# FMC_Connector.net
KiCad netlist of a schematic drawn in Altium Designer
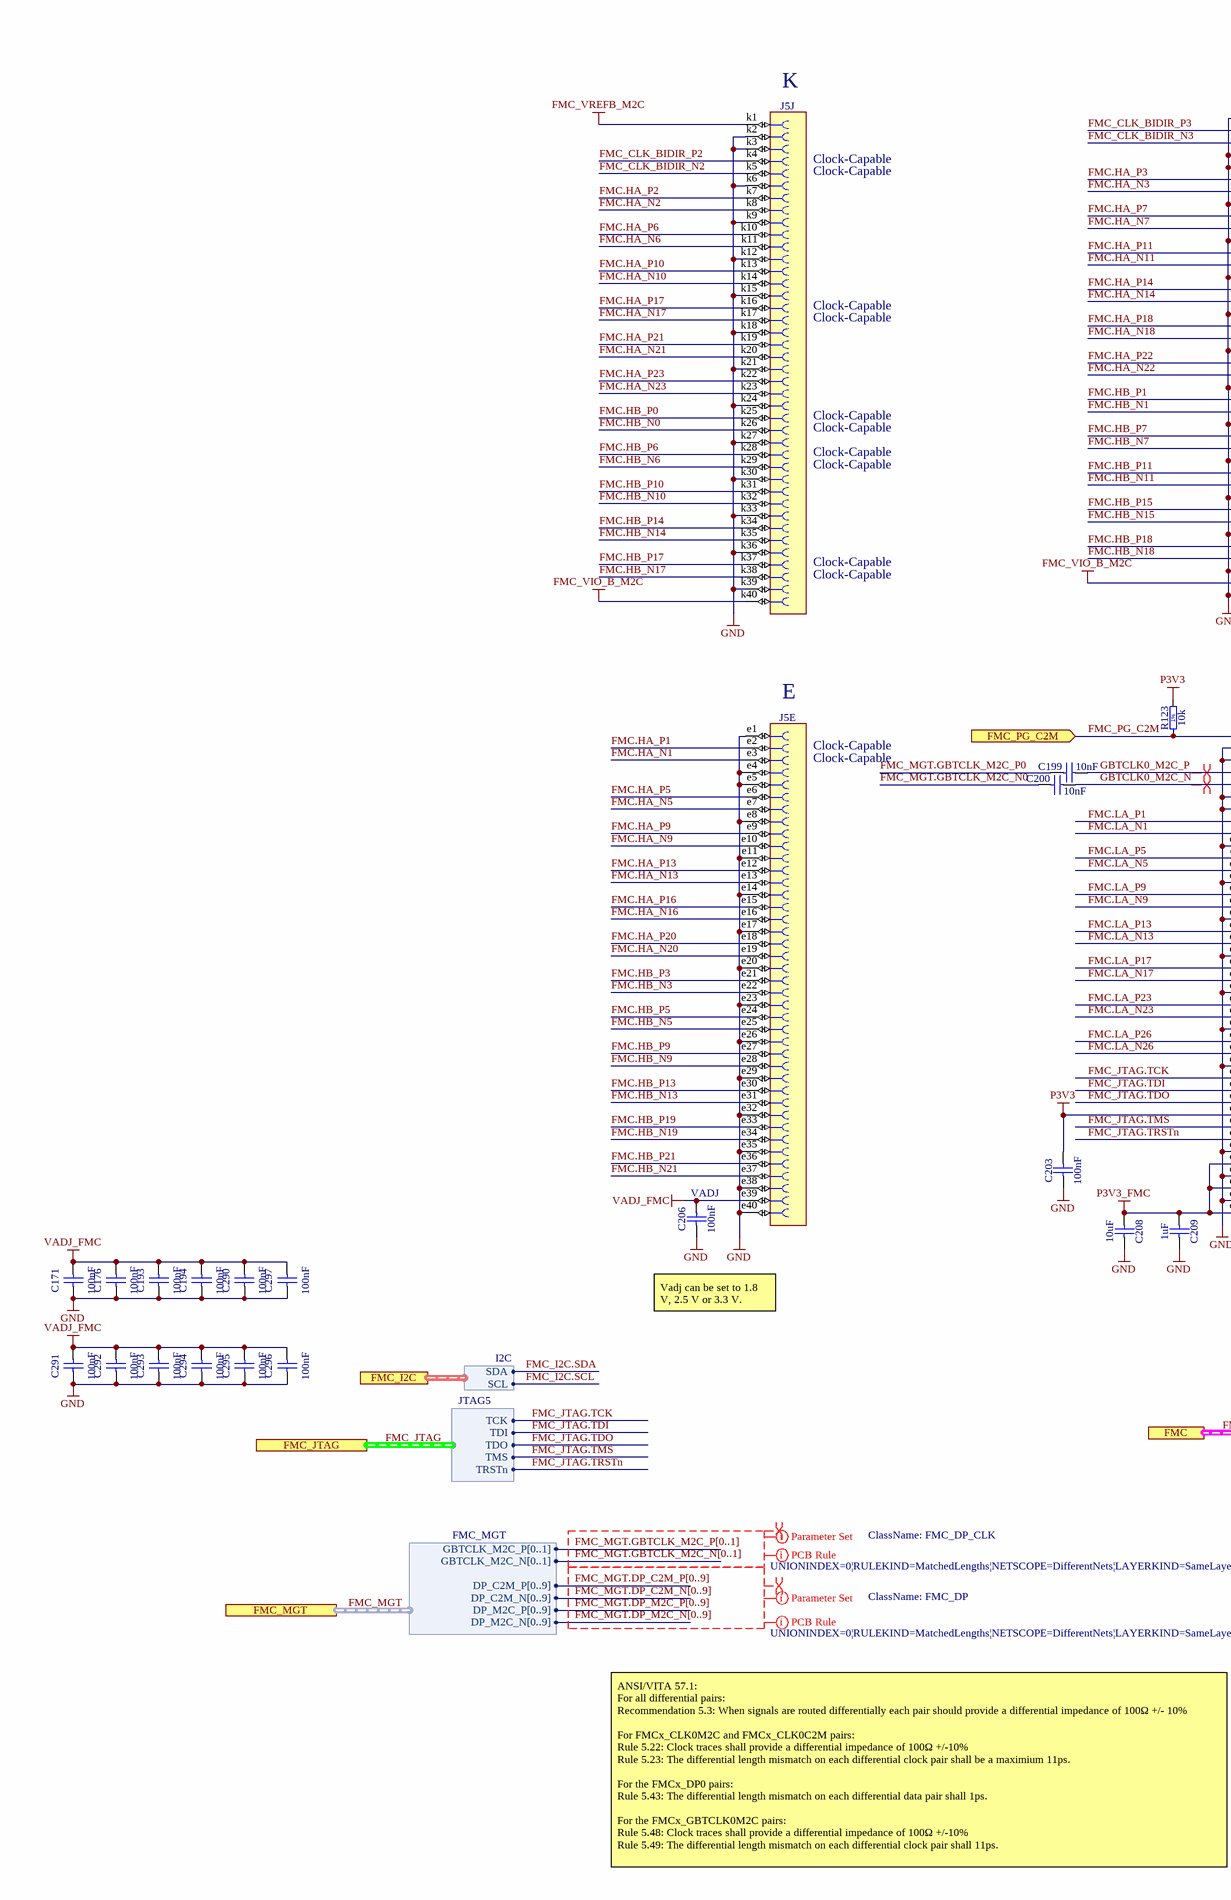
[diagram p0: FMC_Connector.SchDoc, left]
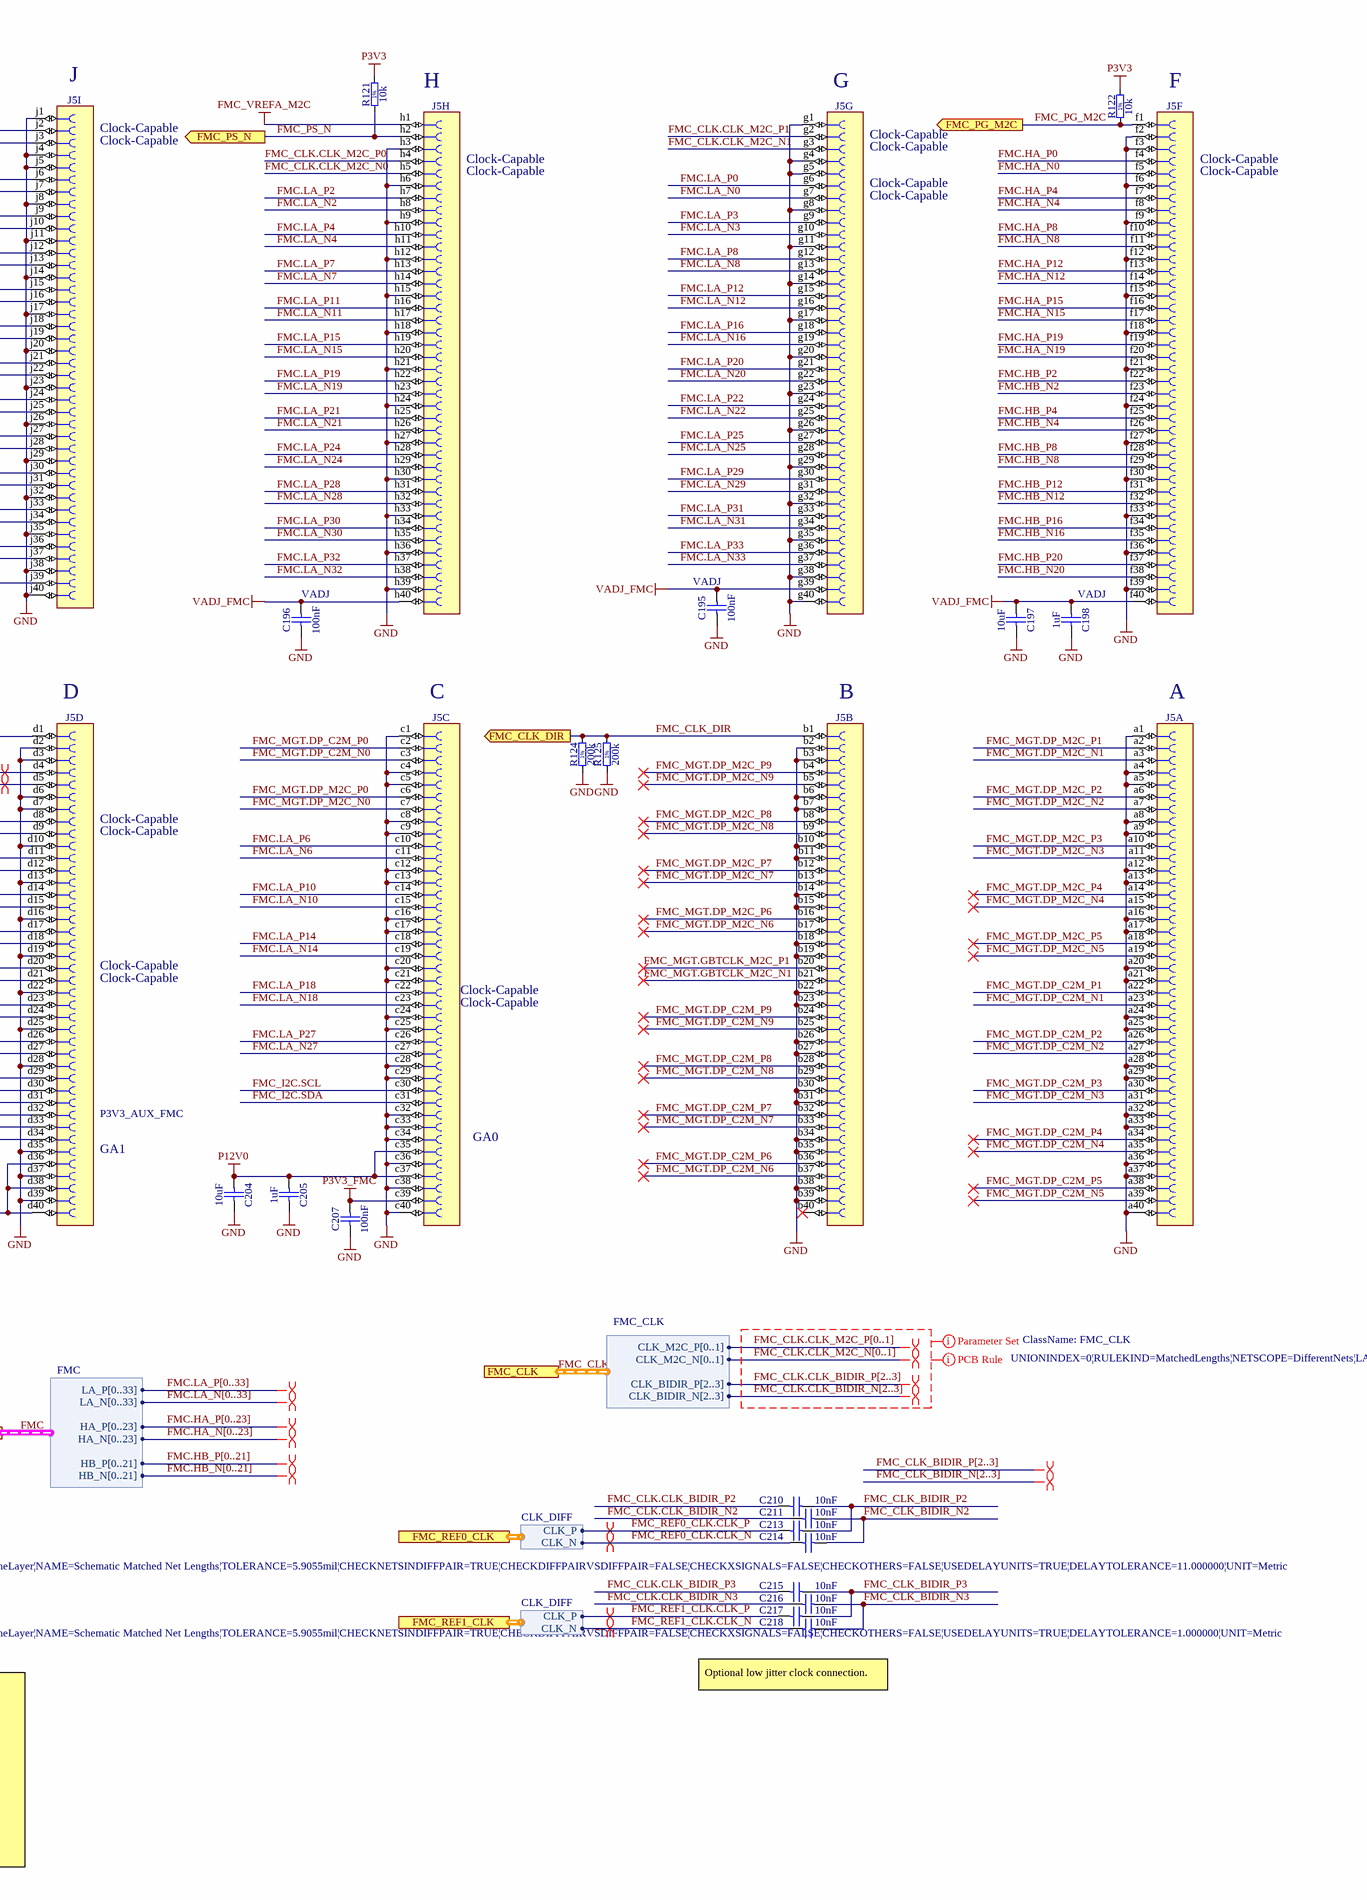
[diagram p1: FMC_Connector.SchDoc, right]

(export (version "E")
  (design (tool "Eeschema 10.0.6"))
  (components
    (comp (ref "C171")
      (value "100nF")
      (footprint "CAPC0603X33N")
      (description "Non-polarised capacitor")
      (fields
        (field (name "PART NUMBER") "CC0201_100NF_6.3V_10%_X5R")
        (field (name "VOLTAGE") "6.3V")
        (field (name "AUTHOR") "CERN DEM JLC")
      )
      (libsource (lib "Capacitors") (part "Capacitor - non polarized"))
    )
    (comp (ref "C176")
      (value "100nF")
      (footprint "CAPC0603X33N")
      (description "Non-polarised capacitor")
      (fields
        (field (name "PART NUMBER") "CC0201_100NF_6.3V_10%_X5R")
        (field (name "VOLTAGE") "6.3V")
        (field (name "AUTHOR") "CERN DEM JLC")
      )
      (libsource (lib "Capacitors") (part "Capacitor - non polarized"))
    )
    (comp (ref "C193")
      (value "100nF")
      (footprint "CAPC0603X33N")
      (description "Non-polarised capacitor")
      (fields
        (field (name "PART NUMBER") "CC0201_100NF_6.3V_10%_X5R")
        (field (name "VOLTAGE") "6.3V")
        (field (name "AUTHOR") "CERN DEM JLC")
      )
      (libsource (lib "Capacitors") (part "Capacitor - non polarized"))
    )
    (comp (ref "C194")
      (value "100nF")
      (footprint "CAPC0603X33N")
      (description "Non-polarised capacitor")
      (fields
        (field (name "PART NUMBER") "CC0201_100NF_6.3V_10%_X5R")
        (field (name "VOLTAGE") "6.3V")
        (field (name "AUTHOR") "CERN DEM JLC")
      )
      (libsource (lib "Capacitors") (part "Capacitor - non polarized"))
    )
    (comp (ref "C195")
      (value "100nF")
      (footprint "CAPC1005X55N")
      (description "Non-polarised capacitor")
      (fields
        (field (name "PART NUMBER") "CC0402_100NF_25V_10%_X7R_YUDEN_TMK105B7104KVHF")
        (field (name "VOLTAGE") "25V")
        (field (name "AUTHOR") "CERN DEM JLC")
      )
      (libsource (lib "Capacitors") (part "Capacitor - non polarized"))
    )
    (comp (ref "C196")
      (value "100nF")
      (footprint "CAPC1005X55N")
      (description "Non-polarised capacitor")
      (fields
        (field (name "PART NUMBER") "CC0402_100NF_25V_10%_X7R_YUDEN_TMK105B7104KVHF")
        (field (name "VOLTAGE") "25V")
        (field (name "AUTHOR") "CERN DEM JLC")
      )
      (libsource (lib "Capacitors") (part "Capacitor - non polarized"))
    )
    (comp (ref "C197")
      (value "10uF")
      (footprint "CAPC2012X95N")
      (description "Non-polarised capacitor")
      (fields
        (field (name "PART NUMBER") "CC0805_10UF_25V_10%_X5R")
        (field (name "VOLTAGE") "25V")
        (field (name "AUTHOR") "CERN DEM JLC")
      )
      (libsource (lib "Capacitors") (part "Capacitor - non polarized"))
    )
    (comp (ref "C198")
      (value "1uF")
      (footprint "CAPC1005X55N")
      (description "Non-polarised capacitor")
      (fields
        (field (name "PART NUMBER") "CC0402_1UF_16V_10%_X5R")
        (field (name "VOLTAGE") "16V")
        (field (name "AUTHOR") "CERN DEM JLC")
      )
      (libsource (lib "Capacitors") (part "Capacitor - non polarized"))
    )
    (comp (ref "C199")
      (value "10nF")
      (footprint "CAPC1005X55N")
      (description "Non-polarised capacitor")
      (fields
        (field (name "PART NUMBER") "CC0402_10NF_16V_10%_X7R")
        (field (name "VOLTAGE") "16V")
        (field (name "AUTHOR") "CERN DEM JLC")
      )
      (libsource (lib "Capacitors") (part "Capacitor - non polarized"))
    )
    (comp (ref "C200")
      (value "10nF")
      (footprint "CAPC1005X55N")
      (description "Non-polarised capacitor")
      (fields
        (field (name "PART NUMBER") "CC0402_10NF_16V_10%_X7R")
        (field (name "VOLTAGE") "16V")
        (field (name "AUTHOR") "CERN DEM JLC")
      )
      (libsource (lib "Capacitors") (part "Capacitor - non polarized"))
    )
    (comp (ref "C203")
      (value "100nF")
      (footprint "CAPC1005X55N")
      (description "Non-polarised capacitor")
      (fields
        (field (name "PART NUMBER") "CC0402_100NF_25V_10%_X7R_YUDEN_TMK105B7104KVHF")
        (field (name "VOLTAGE") "25V")
        (field (name "AUTHOR") "CERN DEM JLC")
      )
      (libsource (lib "Capacitors") (part "Capacitor - non polarized"))
    )
    (comp (ref "C204")
      (value "10uF")
      (footprint "CAPC2012X95N")
      (description "Non-polarised capacitor")
      (fields
        (field (name "PART NUMBER") "CC0805_10UF_25V_10%_X5R")
        (field (name "VOLTAGE") "25V")
        (field (name "AUTHOR") "CERN DEM JLC")
      )
      (libsource (lib "Capacitors") (part "Capacitor - non polarized"))
    )
    (comp (ref "C205")
      (value "1uF")
      (footprint "CAPC1005X55N")
      (description "Non-polarised capacitor")
      (fields
        (field (name "PART NUMBER") "CC0402_1UF_16V_10%_X5R")
        (field (name "VOLTAGE") "16V")
        (field (name "AUTHOR") "CERN DEM JLC")
      )
      (libsource (lib "Capacitors") (part "Capacitor - non polarized"))
    )
    (comp (ref "C206")
      (value "100nF")
      (footprint "CAPC1005X55N")
      (description "Non-polarised capacitor")
      (fields
        (field (name "PART NUMBER") "CC0402_100NF_25V_10%_X7R_YUDEN_TMK105B7104KVHF")
        (field (name "VOLTAGE") "25V")
        (field (name "AUTHOR") "CERN DEM JLC")
      )
      (libsource (lib "Capacitors") (part "Capacitor - non polarized"))
    )
    (comp (ref "C207")
      (value "100nF")
      (footprint "CAPC1005X55N")
      (description "Non-polarised capacitor")
      (fields
        (field (name "PART NUMBER") "CC0402_100NF_25V_10%_X7R_YUDEN_TMK105B7104KVHF")
        (field (name "VOLTAGE") "25V")
        (field (name "AUTHOR") "CERN DEM JLC")
      )
      (libsource (lib "Capacitors") (part "Capacitor - non polarized"))
    )
    (comp (ref "C208")
      (value "10uF")
      (footprint "CAPC2012X95N")
      (description "Non-polarised capacitor")
      (fields
        (field (name "PART NUMBER") "CC0805_10UF_25V_10%_X5R")
        (field (name "VOLTAGE") "25V")
        (field (name "AUTHOR") "CERN DEM JLC")
      )
      (libsource (lib "Capacitors") (part "Capacitor - non polarized"))
    )
    (comp (ref "C209")
      (value "1uF")
      (footprint "CAPC1005X55N")
      (description "Non-polarised capacitor")
      (fields
        (field (name "PART NUMBER") "CC0402_1UF_16V_10%_X5R")
        (field (name "VOLTAGE") "16V")
        (field (name "AUTHOR") "CERN DEM JLC")
      )
      (libsource (lib "Capacitors") (part "Capacitor - non polarized"))
    )
    (comp (ref "C210")
      (value "10nF")
      (footprint "CAPC1005X55N")
      (description "Non-polarised capacitor")
      (fields
        (field (name "PART NUMBER") "CC0402_10NF_16V_10%_X7R")
        (field (name "VOLTAGE") "16V")
        (field (name "AUTHOR") "CERN DEM JLC")
      )
      (libsource (lib "Capacitors") (part "Capacitor - non polarized"))
    )
    (comp (ref "C211")
      (value "10nF")
      (footprint "CAPC1005X55N")
      (description "Non-polarised capacitor")
      (fields
        (field (name "PART NUMBER") "CC0402_10NF_16V_10%_X7R")
        (field (name "VOLTAGE") "16V")
        (field (name "AUTHOR") "CERN DEM JLC")
      )
      (libsource (lib "Capacitors") (part "Capacitor - non polarized"))
    )
    (comp (ref "C213")
      (value "10nF")
      (footprint "CAPC1005X55N")
      (description "Non-polarised capacitor")
      (fields
        (field (name "PART NUMBER") "CC0402_10NF_16V_10%_X7R")
        (field (name "VOLTAGE") "16V")
        (field (name "AUTHOR") "CERN DEM JLC")
      )
      (libsource (lib "Capacitors") (part "Capacitor - non polarized"))
    )
    (comp (ref "C214")
      (value "10nF")
      (footprint "CAPC1005X55N")
      (description "Non-polarised capacitor")
      (fields
        (field (name "PART NUMBER") "CC0402_10NF_16V_10%_X7R")
        (field (name "VOLTAGE") "16V")
        (field (name "AUTHOR") "CERN DEM JLC")
      )
      (libsource (lib "Capacitors") (part "Capacitor - non polarized"))
    )
    (comp (ref "C215")
      (value "10nF")
      (footprint "CAPC1005X55N")
      (description "Non-polarised capacitor")
      (fields
        (field (name "PART NUMBER") "CC0402_10NF_16V_10%_X7R")
        (field (name "VOLTAGE") "16V")
        (field (name "AUTHOR") "CERN DEM JLC")
      )
      (libsource (lib "Capacitors") (part "Capacitor - non polarized"))
    )
    (comp (ref "C216")
      (value "10nF")
      (footprint "CAPC1005X55N")
      (description "Non-polarised capacitor")
      (fields
        (field (name "PART NUMBER") "CC0402_10NF_16V_10%_X7R")
        (field (name "VOLTAGE") "16V")
        (field (name "AUTHOR") "CERN DEM JLC")
      )
      (libsource (lib "Capacitors") (part "Capacitor - non polarized"))
    )
    (comp (ref "C217")
      (value "10nF")
      (footprint "CAPC1005X55N")
      (description "Non-polarised capacitor")
      (fields
        (field (name "PART NUMBER") "CC0402_10NF_16V_10%_X7R")
        (field (name "VOLTAGE") "16V")
        (field (name "AUTHOR") "CERN DEM JLC")
      )
      (libsource (lib "Capacitors") (part "Capacitor - non polarized"))
    )
    (comp (ref "C218")
      (value "10nF")
      (footprint "CAPC1005X55N")
      (description "Non-polarised capacitor")
      (fields
        (field (name "PART NUMBER") "CC0402_10NF_16V_10%_X7R")
        (field (name "VOLTAGE") "16V")
        (field (name "AUTHOR") "CERN DEM JLC")
      )
      (libsource (lib "Capacitors") (part "Capacitor - non polarized"))
    )
    (comp (ref "C290")
      (value "100nF")
      (footprint "CAPC0603X33N")
      (description "Non-polarised capacitor")
      (fields
        (field (name "PART NUMBER") "CC0201_100NF_6.3V_10%_X5R")
        (field (name "VOLTAGE") "6.3V")
        (field (name "AUTHOR") "CERN DEM JLC")
      )
      (libsource (lib "Capacitors") (part "Capacitor - non polarized"))
    )
    (comp (ref "C291")
      (value "100nF")
      (footprint "CAPC0603X33N")
      (description "Non-polarised capacitor")
      (fields
        (field (name "PART NUMBER") "CC0201_100NF_6.3V_10%_X5R")
        (field (name "VOLTAGE") "6.3V")
        (field (name "AUTHOR") "CERN DEM JLC")
      )
      (libsource (lib "Capacitors") (part "Capacitor - non polarized"))
    )
    (comp (ref "C292")
      (value "100nF")
      (footprint "CAPC0603X33N")
      (description "Non-polarised capacitor")
      (fields
        (field (name "PART NUMBER") "CC0201_100NF_6.3V_10%_X5R")
        (field (name "VOLTAGE") "6.3V")
        (field (name "AUTHOR") "CERN DEM JLC")
      )
      (libsource (lib "Capacitors") (part "Capacitor - non polarized"))
    )
    (comp (ref "C293")
      (value "100nF")
      (footprint "CAPC0603X33N")
      (description "Non-polarised capacitor")
      (fields
        (field (name "PART NUMBER") "CC0201_100NF_6.3V_10%_X5R")
        (field (name "VOLTAGE") "6.3V")
        (field (name "AUTHOR") "CERN DEM JLC")
      )
      (libsource (lib "Capacitors") (part "Capacitor - non polarized"))
    )
    (comp (ref "C294")
      (value "100nF")
      (footprint "CAPC0603X33N")
      (description "Non-polarised capacitor")
      (fields
        (field (name "PART NUMBER") "CC0201_100NF_6.3V_10%_X5R")
        (field (name "VOLTAGE") "6.3V")
        (field (name "AUTHOR") "CERN DEM JLC")
      )
      (libsource (lib "Capacitors") (part "Capacitor - non polarized"))
    )
    (comp (ref "C295")
      (value "100nF")
      (footprint "CAPC0603X33N")
      (description "Non-polarised capacitor")
      (fields
        (field (name "PART NUMBER") "CC0201_100NF_6.3V_10%_X5R")
        (field (name "VOLTAGE") "6.3V")
        (field (name "AUTHOR") "CERN DEM JLC")
      )
      (libsource (lib "Capacitors") (part "Capacitor - non polarized"))
    )
    (comp (ref "C296")
      (value "100nF")
      (footprint "CAPC0603X33N")
      (description "Non-polarised capacitor")
      (fields
        (field (name "PART NUMBER") "CC0201_100NF_6.3V_10%_X5R")
        (field (name "VOLTAGE") "6.3V")
        (field (name "AUTHOR") "CERN DEM JLC")
      )
      (libsource (lib "Capacitors") (part "Capacitor - non polarized"))
    )
    (comp (ref "C297")
      (value "100nF")
      (footprint "CAPC0603X33N")
      (description "Non-polarised capacitor")
      (fields
        (field (name "PART NUMBER") "CC0201_100NF_6.3V_10%_X5R")
        (field (name "VOLTAGE") "6.3V")
        (field (name "AUTHOR") "CERN DEM JLC")
      )
      (libsource (lib "Capacitors") (part "Capacitor - non polarized"))
    )
    (comp (ref "J5")
      (value "VITA 57")
      (footprint "SAMTEC_ASP-134486-01")
      (description "Connector VITA 57, 400 Female contacts in 10 row abcdefghj")
      (fields
        (field (name "PART NUMBER") "SAMTEC_ASP-134486-01")
        (field (name "MANUFACTURER") "SAMTEC")
        (field (name "AUTHOR") "CERN DEM JLC")
      )
      (libsource (lib "Connectors") (part "Connector VITA 57 400 Female (abcdefghjk)"))
    )
    (comp (ref "R121")
      (value "10k")
      (footprint "RESC1005X40N")
      (description "Resistor - 1%")
      (fields
        (field (name "PART NUMBER") "R0402_10K_1%_0.0625W_100PPM")
        (field (name "POWER") "0.0625W")
        (field (name "AUTHOR") "CERN DEM JLC")
      )
      (libsource (lib "Resistors") (part "Resistor - 1%"))
    )
    (comp (ref "R122")
      (value "10k")
      (footprint "RESC1005X40N")
      (description "Resistor - 1%")
      (fields
        (field (name "PART NUMBER") "R0402_10K_1%_0.0625W_100PPM")
        (field (name "POWER") "0.0625W")
        (field (name "AUTHOR") "CERN DEM JLC")
      )
      (libsource (lib "Resistors") (part "Resistor - 1%"))
    )
    (comp (ref "R123")
      (value "10k")
      (footprint "RESC1005X40N")
      (description "Resistor - 1%")
      (fields
        (field (name "PART NUMBER") "R0402_10K_1%_0.0625W_100PPM")
        (field (name "POWER") "0.0625W")
        (field (name "AUTHOR") "CERN DEM JLC")
      )
      (libsource (lib "Resistors") (part "Resistor - 1%"))
    )
    (comp (ref "R124")
      (value "200k")
      (footprint "RESC1005X40N")
      (description "Resistor - 1%")
      (fields
        (field (name "PART NUMBER") "R0402_200K_1%_0.0625W_100PPM")
        (field (name "POWER") "0.0625W")
        (field (name "AUTHOR") "CERN DEM JLC")
      )
      (libsource (lib "Resistors") (part "Resistor - 1%"))
    )
    (comp (ref "R125")
      (value "200k")
      (footprint "RESC1005X40N")
      (description "Resistor - 1%")
      (fields
        (field (name "PART NUMBER") "R0402_200K_1%_0.0625W_100PPM")
        (field (name "POWER") "0.0625W")
        (field (name "AUTHOR") "CERN DEM JLC")
      )
      (libsource (lib "Resistors") (part "Resistor - 1%"))
    )
  )
  (nets
    (net (code "7") (name "/FMC.HA_N0") (class "Default")
      (node (ref "J5") (pin "f5") (pinfunction "f5_f5") (pintype "bidirectional"))
    )
    (net (code "8") (name "/FMC.HA_N1") (class "Default")
      (node (ref "J5") (pin "e3") (pinfunction "e3_e3") (pintype "bidirectional"))
    )
    (net (code "9") (name "/FMC.HA_N2") (class "Default")
      (node (ref "J5") (pin "k8") (pinfunction "k8_k8") (pintype "bidirectional"))
    )
    (net (code "10") (name "/FMC.HA_N3") (class "Default")
      (node (ref "J5") (pin "j7") (pinfunction "j7_j7") (pintype "bidirectional"))
    )
    (net (code "11") (name "/FMC.HA_N4") (class "Default")
      (node (ref "J5") (pin "f8") (pinfunction "f8_f8") (pintype "bidirectional"))
    )
    (net (code "12") (name "/FMC.HA_N5") (class "Default")
      (node (ref "J5") (pin "e7") (pinfunction "e7_e7") (pintype "bidirectional"))
    )
    (net (code "13") (name "/FMC.HA_N6") (class "Default")
      (node (ref "J5") (pin "k11") (pinfunction "k11_k11") (pintype "bidirectional"))
    )
    (net (code "14") (name "/FMC.HA_N7") (class "Default")
      (node (ref "J5") (pin "j10") (pinfunction "j10_j10") (pintype "bidirectional"))
    )
    (net (code "15") (name "/FMC.HA_N8") (class "Default")
      (node (ref "J5") (pin "f11") (pinfunction "f11_f11") (pintype "bidirectional"))
    )
    (net (code "16") (name "/FMC.HA_N9") (class "Default")
      (node (ref "J5") (pin "e10") (pinfunction "e10_e10") (pintype "bidirectional"))
    )
    (net (code "17") (name "/FMC.HA_N10") (class "Default")
      (node (ref "J5") (pin "k14") (pinfunction "k14_k14") (pintype "bidirectional"))
    )
    (net (code "18") (name "/FMC.HA_N11") (class "Default")
      (node (ref "J5") (pin "j13") (pinfunction "j13_j13") (pintype "bidirectional"))
    )
    (net (code "19") (name "/FMC.HA_N12") (class "Default")
      (node (ref "J5") (pin "f14") (pinfunction "f14_f14") (pintype "bidirectional"))
    )
    (net (code "20") (name "/FMC.HA_N13") (class "Default")
      (node (ref "J5") (pin "e13") (pinfunction "e13_e13") (pintype "bidirectional"))
    )
    (net (code "21") (name "/FMC.HA_N14") (class "Default")
      (node (ref "J5") (pin "j16") (pinfunction "j16_j16") (pintype "bidirectional"))
    )
    (net (code "22") (name "/FMC.HA_N15") (class "Default")
      (node (ref "J5") (pin "f17") (pinfunction "f17_f17") (pintype "bidirectional"))
    )
    (net (code "23") (name "/FMC.HA_N16") (class "Default")
      (node (ref "J5") (pin "e16") (pinfunction "e16_e16") (pintype "bidirectional"))
    )
    (net (code "24") (name "/FMC.HA_N17") (class "Default")
      (node (ref "J5") (pin "k17") (pinfunction "k17_k17") (pintype "bidirectional"))
    )
    (net (code "25") (name "/FMC.HA_N18") (class "Default")
      (node (ref "J5") (pin "j19") (pinfunction "j19_j19") (pintype "bidirectional"))
    )
    (net (code "26") (name "/FMC.HA_N19") (class "Default")
      (node (ref "J5") (pin "f20") (pinfunction "f20_f20") (pintype "bidirectional"))
    )
    (net (code "27") (name "/FMC.HA_N20") (class "Default")
      (node (ref "J5") (pin "e19") (pinfunction "e19_e19") (pintype "bidirectional"))
    )
    (net (code "28") (name "/FMC.HA_N21") (class "Default")
      (node (ref "J5") (pin "k20") (pinfunction "k20_k20") (pintype "bidirectional"))
    )
    (net (code "29") (name "/FMC.HA_N22") (class "Default")
      (node (ref "J5") (pin "j22") (pinfunction "j22_j22") (pintype "bidirectional"))
    )
    (net (code "30") (name "/FMC.HA_N23") (class "Default")
      (node (ref "J5") (pin "k23") (pinfunction "k23_k23") (pintype "bidirectional"))
    )
    (net (code "32") (name "/FMC.HA_P0") (class "Default")
      (node (ref "J5") (pin "f4") (pinfunction "f4_f4") (pintype "bidirectional"))
    )
    (net (code "33") (name "/FMC.HA_P1") (class "Default")
      (node (ref "J5") (pin "e2") (pinfunction "e2_e2") (pintype "bidirectional"))
    )
    (net (code "34") (name "/FMC.HA_P2") (class "Default")
      (node (ref "J5") (pin "k7") (pinfunction "k7_k7") (pintype "bidirectional"))
    )
    (net (code "35") (name "/FMC.HA_P3") (class "Default")
      (node (ref "J5") (pin "j6") (pinfunction "j6_j6") (pintype "bidirectional"))
    )
    (net (code "36") (name "/FMC.HA_P4") (class "Default")
      (node (ref "J5") (pin "f7") (pinfunction "f7_f7") (pintype "bidirectional"))
    )
    (net (code "37") (name "/FMC.HA_P5") (class "Default")
      (node (ref "J5") (pin "e6") (pinfunction "e6_e6") (pintype "bidirectional"))
    )
    (net (code "38") (name "/FMC.HA_P6") (class "Default")
      (node (ref "J5") (pin "k10") (pinfunction "k10_k10") (pintype "bidirectional"))
    )
    (net (code "39") (name "/FMC.HA_P7") (class "Default")
      (node (ref "J5") (pin "j9") (pinfunction "j9_j9") (pintype "bidirectional"))
    )
    (net (code "40") (name "/FMC.HA_P8") (class "Default")
      (node (ref "J5") (pin "f10") (pinfunction "f10_f10") (pintype "bidirectional"))
    )
    (net (code "41") (name "/FMC.HA_P9") (class "Default")
      (node (ref "J5") (pin "e9") (pinfunction "e9_e9") (pintype "bidirectional"))
    )
    (net (code "42") (name "/FMC.HA_P10") (class "Default")
      (node (ref "J5") (pin "k13") (pinfunction "k13_k13") (pintype "bidirectional"))
    )
    (net (code "43") (name "/FMC.HA_P11") (class "Default")
      (node (ref "J5") (pin "j12") (pinfunction "j12_j12") (pintype "bidirectional"))
    )
    (net (code "44") (name "/FMC.HA_P12") (class "Default")
      (node (ref "J5") (pin "f13") (pinfunction "f13_f13") (pintype "bidirectional"))
    )
    (net (code "45") (name "/FMC.HA_P13") (class "Default")
      (node (ref "J5") (pin "e12") (pinfunction "e12_e12") (pintype "bidirectional"))
    )
    (net (code "46") (name "/FMC.HA_P14") (class "Default")
      (node (ref "J5") (pin "j15") (pinfunction "j15_j15") (pintype "bidirectional"))
    )
    (net (code "47") (name "/FMC.HA_P15") (class "Default")
      (node (ref "J5") (pin "f16") (pinfunction "f16_f16") (pintype "bidirectional"))
    )
    (net (code "48") (name "/FMC.HA_P16") (class "Default")
      (node (ref "J5") (pin "e15") (pinfunction "e15_e15") (pintype "bidirectional"))
    )
    (net (code "49") (name "/FMC.HA_P17") (class "Default")
      (node (ref "J5") (pin "k16") (pinfunction "k16_k16") (pintype "bidirectional"))
    )
    (net (code "50") (name "/FMC.HA_P18") (class "Default")
      (node (ref "J5") (pin "j18") (pinfunction "j18_j18") (pintype "bidirectional"))
    )
    (net (code "51") (name "/FMC.HA_P19") (class "Default")
      (node (ref "J5") (pin "f19") (pinfunction "f19_f19") (pintype "bidirectional"))
    )
    (net (code "52") (name "/FMC.HA_P20") (class "Default")
      (node (ref "J5") (pin "e18") (pinfunction "e18_e18") (pintype "bidirectional"))
    )
    (net (code "53") (name "/FMC.HA_P21") (class "Default")
      (node (ref "J5") (pin "k19") (pinfunction "k19_k19") (pintype "bidirectional"))
    )
    (net (code "54") (name "/FMC.HA_P22") (class "Default")
      (node (ref "J5") (pin "j21") (pinfunction "j21_j21") (pintype "bidirectional"))
    )
    (net (code "55") (name "/FMC.HA_P23") (class "Default")
      (node (ref "J5") (pin "k22") (pinfunction "k22_k22") (pintype "bidirectional"))
    )
    (net (code "57") (name "/FMC.HB_N0") (class "Default")
      (node (ref "J5") (pin "k26") (pinfunction "k26_k26") (pintype "bidirectional"))
    )
    (net (code "58") (name "/FMC.HB_N1") (class "Default")
      (node (ref "J5") (pin "j25") (pinfunction "j25_j25") (pintype "bidirectional"))
    )
    (net (code "59") (name "/FMC.HB_N2") (class "Default")
      (node (ref "J5") (pin "f23") (pinfunction "f23_f23") (pintype "bidirectional"))
    )
    (net (code "60") (name "/FMC.HB_N3") (class "Default")
      (node (ref "J5") (pin "e22") (pinfunction "e22_e22") (pintype "bidirectional"))
    )
    (net (code "61") (name "/FMC.HB_N4") (class "Default")
      (node (ref "J5") (pin "f26") (pinfunction "f26_f26") (pintype "bidirectional"))
    )
    (net (code "62") (name "/FMC.HB_N5") (class "Default")
      (node (ref "J5") (pin "e25") (pinfunction "e25_e25") (pintype "bidirectional"))
    )
    (net (code "63") (name "/FMC.HB_N6") (class "Default")
      (node (ref "J5") (pin "k29") (pinfunction "k29_k29") (pintype "bidirectional"))
    )
    (net (code "64") (name "/FMC.HB_N7") (class "Default")
      (node (ref "J5") (pin "j28") (pinfunction "j28_j28") (pintype "bidirectional"))
    )
    (net (code "65") (name "/FMC.HB_N8") (class "Default")
      (node (ref "J5") (pin "f29") (pinfunction "f29_f29") (pintype "bidirectional"))
    )
    (net (code "66") (name "/FMC.HB_N9") (class "Default")
      (node (ref "J5") (pin "e28") (pinfunction "e28_e28") (pintype "bidirectional"))
    )
    (net (code "67") (name "/FMC.HB_N10") (class "Default")
      (node (ref "J5") (pin "k32") (pinfunction "k32_k32") (pintype "bidirectional"))
    )
    (net (code "68") (name "/FMC.HB_N11") (class "Default")
      (node (ref "J5") (pin "j31") (pinfunction "j31_j31") (pintype "bidirectional"))
    )
    (net (code "69") (name "/FMC.HB_N12") (class "Default")
      (node (ref "J5") (pin "f32") (pinfunction "f32_f32") (pintype "bidirectional"))
    )
    (net (code "70") (name "/FMC.HB_N13") (class "Default")
      (node (ref "J5") (pin "e31") (pinfunction "e31_e31") (pintype "bidirectional"))
    )
    (net (code "71") (name "/FMC.HB_N14") (class "Default")
      (node (ref "J5") (pin "k35") (pinfunction "k35_k35") (pintype "bidirectional"))
    )
    (net (code "72") (name "/FMC.HB_N15") (class "Default")
      (node (ref "J5") (pin "j34") (pinfunction "j34_j34") (pintype "bidirectional"))
    )
    (net (code "73") (name "/FMC.HB_N16") (class "Default")
      (node (ref "J5") (pin "f35") (pinfunction "f35_f35") (pintype "bidirectional"))
    )
    (net (code "74") (name "/FMC.HB_N17") (class "Default")
      (node (ref "J5") (pin "k38") (pinfunction "k38_k38") (pintype "bidirectional"))
    )
    (net (code "75") (name "/FMC.HB_N18") (class "Default")
      (node (ref "J5") (pin "j37") (pinfunction "j37_j37") (pintype "bidirectional"))
    )
    (net (code "76") (name "/FMC.HB_N19") (class "Default")
      (node (ref "J5") (pin "e34") (pinfunction "e34_e34") (pintype "bidirectional"))
    )
    (net (code "77") (name "/FMC.HB_N20") (class "Default")
      (node (ref "J5") (pin "f38") (pinfunction "f38_f38") (pintype "bidirectional"))
    )
    (net (code "78") (name "/FMC.HB_N21") (class "Default")
      (node (ref "J5") (pin "e37") (pinfunction "e37_e37") (pintype "bidirectional"))
    )
    (net (code "80") (name "/FMC.HB_P0") (class "Default")
      (node (ref "J5") (pin "k25") (pinfunction "k25_k25") (pintype "bidirectional"))
    )
    (net (code "81") (name "/FMC.HB_P1") (class "Default")
      (node (ref "J5") (pin "j24") (pinfunction "j24_j24") (pintype "bidirectional"))
    )
    (net (code "82") (name "/FMC.HB_P2") (class "Default")
      (node (ref "J5") (pin "f22") (pinfunction "f22_f22") (pintype "bidirectional"))
    )
    (net (code "83") (name "/FMC.HB_P3") (class "Default")
      (node (ref "J5") (pin "e21") (pinfunction "e21_e21") (pintype "bidirectional"))
    )
    (net (code "84") (name "/FMC.HB_P4") (class "Default")
      (node (ref "J5") (pin "f25") (pinfunction "f25_f25") (pintype "bidirectional"))
    )
    (net (code "85") (name "/FMC.HB_P5") (class "Default")
      (node (ref "J5") (pin "e24") (pinfunction "e24_e24") (pintype "bidirectional"))
    )
    (net (code "86") (name "/FMC.HB_P6") (class "Default")
      (node (ref "J5") (pin "k28") (pinfunction "k28_k28") (pintype "bidirectional"))
    )
    (net (code "87") (name "/FMC.HB_P7") (class "Default")
      (node (ref "J5") (pin "j27") (pinfunction "j27_j27") (pintype "bidirectional"))
    )
    (net (code "88") (name "/FMC.HB_P8") (class "Default")
      (node (ref "J5") (pin "f28") (pinfunction "f28_f28") (pintype "bidirectional"))
    )
    (net (code "89") (name "/FMC.HB_P9") (class "Default")
      (node (ref "J5") (pin "e27") (pinfunction "e27_e27") (pintype "bidirectional"))
    )
    (net (code "90") (name "/FMC.HB_P10") (class "Default")
      (node (ref "J5") (pin "k31") (pinfunction "k31_k31") (pintype "bidirectional"))
    )
    (net (code "91") (name "/FMC.HB_P11") (class "Default")
      (node (ref "J5") (pin "j30") (pinfunction "j30_j30") (pintype "bidirectional"))
    )
    (net (code "92") (name "/FMC.HB_P12") (class "Default")
      (node (ref "J5") (pin "f31") (pinfunction "f31_f31") (pintype "bidirectional"))
    )
    (net (code "93") (name "/FMC.HB_P13") (class "Default")
      (node (ref "J5") (pin "e30") (pinfunction "e30_e30") (pintype "bidirectional"))
    )
    (net (code "94") (name "/FMC.HB_P14") (class "Default")
      (node (ref "J5") (pin "k34") (pinfunction "k34_k34") (pintype "bidirectional"))
    )
    (net (code "95") (name "/FMC.HB_P15") (class "Default")
      (node (ref "J5") (pin "j33") (pinfunction "j33_j33") (pintype "bidirectional"))
    )
    (net (code "96") (name "/FMC.HB_P16") (class "Default")
      (node (ref "J5") (pin "f34") (pinfunction "f34_f34") (pintype "bidirectional"))
    )
    (net (code "97") (name "/FMC.HB_P17") (class "Default")
      (node (ref "J5") (pin "k37") (pinfunction "k37_k37") (pintype "bidirectional"))
    )
    (net (code "98") (name "/FMC.HB_P18") (class "Default")
      (node (ref "J5") (pin "j36") (pinfunction "j36_j36") (pintype "bidirectional"))
    )
    (net (code "99") (name "/FMC.HB_P19") (class "Default")
      (node (ref "J5") (pin "e33") (pinfunction "e33_e33") (pintype "bidirectional"))
    )
    (net (code "100") (name "/FMC.HB_P20") (class "Default")
      (node (ref "J5") (pin "f37") (pinfunction "f37_f37") (pintype "bidirectional"))
    )
    (net (code "101") (name "/FMC.HB_P21") (class "Default")
      (node (ref "J5") (pin "e36") (pinfunction "e36_e36") (pintype "bidirectional"))
    )
    (net (code "103") (name "/FMC.LA_N0") (class "Default")
      (node (ref "J5") (pin "g7") (pinfunction "g7_g7") (pintype "bidirectional"))
    )
    (net (code "104") (name "/FMC.LA_N1") (class "Default")
      (node (ref "J5") (pin "d9") (pinfunction "d9_d9") (pintype "bidirectional"))
    )
    (net (code "105") (name "/FMC.LA_N2") (class "Default")
      (node (ref "J5") (pin "h8") (pinfunction "h8_h8") (pintype "bidirectional"))
    )
    (net (code "106") (name "/FMC.LA_N3") (class "Default")
      (node (ref "J5") (pin "g10") (pinfunction "g10_g10") (pintype "bidirectional"))
    )
    (net (code "107") (name "/FMC.LA_N4") (class "Default")
      (node (ref "J5") (pin "h11") (pinfunction "h11_h11") (pintype "bidirectional"))
    )
    (net (code "108") (name "/FMC.LA_N5") (class "Default")
      (node (ref "J5") (pin "d12") (pinfunction "d12_d12") (pintype "bidirectional"))
    )
    (net (code "109") (name "/FMC.LA_N6") (class "Default")
      (node (ref "J5") (pin "c11") (pinfunction "c11_c11") (pintype "bidirectional"))
    )
    (net (code "110") (name "/FMC.LA_N7") (class "Default")
      (node (ref "J5") (pin "h14") (pinfunction "h14_h14") (pintype "bidirectional"))
    )
    (net (code "111") (name "/FMC.LA_N8") (class "Default")
      (node (ref "J5") (pin "g13") (pinfunction "g13_g13") (pintype "bidirectional"))
    )
    (net (code "112") (name "/FMC.LA_N9") (class "Default")
      (node (ref "J5") (pin "d15") (pinfunction "d15_d15") (pintype "bidirectional"))
    )
    (net (code "113") (name "/FMC.LA_N10") (class "Default")
      (node (ref "J5") (pin "c15") (pinfunction "c15_c15") (pintype "bidirectional"))
    )
    (net (code "114") (name "/FMC.LA_N11") (class "Default")
      (node (ref "J5") (pin "h17") (pinfunction "h17_h17") (pintype "bidirectional"))
    )
    (net (code "115") (name "/FMC.LA_N12") (class "Default")
      (node (ref "J5") (pin "g16") (pinfunction "g16_g16") (pintype "bidirectional"))
    )
    (net (code "116") (name "/FMC.LA_N13") (class "Default")
      (node (ref "J5") (pin "d18") (pinfunction "d18_d18") (pintype "bidirectional"))
    )
    (net (code "117") (name "/FMC.LA_N14") (class "Default")
      (node (ref "J5") (pin "c19") (pinfunction "c19_c19") (pintype "bidirectional"))
    )
    (net (code "118") (name "/FMC.LA_N15") (class "Default")
      (node (ref "J5") (pin "h20") (pinfunction "h20_h20") (pintype "bidirectional"))
    )
    (net (code "119") (name "/FMC.LA_N16") (class "Default")
      (node (ref "J5") (pin "g19") (pinfunction "g19_g19") (pintype "bidirectional"))
    )
    (net (code "120") (name "/FMC.LA_N17") (class "Default")
      (node (ref "J5") (pin "d21") (pinfunction "d21_d21") (pintype "bidirectional"))
    )
    (net (code "121") (name "/FMC.LA_N18") (class "Default")
      (node (ref "J5") (pin "c23") (pinfunction "c23_c23") (pintype "bidirectional"))
    )
    (net (code "122") (name "/FMC.LA_N19") (class "Default")
      (node (ref "J5") (pin "h23") (pinfunction "h23_h23") (pintype "bidirectional"))
    )
    (net (code "123") (name "/FMC.LA_N20") (class "Default")
      (node (ref "J5") (pin "g22") (pinfunction "g22_g22") (pintype "bidirectional"))
    )
    (net (code "124") (name "/FMC.LA_N21") (class "Default")
      (node (ref "J5") (pin "h26") (pinfunction "h26_h26") (pintype "bidirectional"))
    )
    (net (code "125") (name "/FMC.LA_N22") (class "Default")
      (node (ref "J5") (pin "g25") (pinfunction "g25_g25") (pintype "bidirectional"))
    )
    (net (code "126") (name "/FMC.LA_N23") (class "Default")
      (node (ref "J5") (pin "d24") (pinfunction "d24_d24") (pintype "bidirectional"))
    )
    (net (code "127") (name "/FMC.LA_N24") (class "Default")
      (node (ref "J5") (pin "h29") (pinfunction "h29_h29") (pintype "bidirectional"))
    )
    (net (code "128") (name "/FMC.LA_N25") (class "Default")
      (node (ref "J5") (pin "g28") (pinfunction "g28_g28") (pintype "bidirectional"))
    )
    (net (code "129") (name "/FMC.LA_N26") (class "Default")
      (node (ref "J5") (pin "d27") (pinfunction "d27_d27") (pintype "bidirectional"))
    )
    (net (code "130") (name "/FMC.LA_N27") (class "Default")
      (node (ref "J5") (pin "c27") (pinfunction "c27_c27") (pintype "bidirectional"))
    )
    (net (code "131") (name "/FMC.LA_N28") (class "Default")
      (node (ref "J5") (pin "h32") (pinfunction "h32_h32") (pintype "bidirectional"))
    )
    (net (code "132") (name "/FMC.LA_N29") (class "Default")
      (node (ref "J5") (pin "g31") (pinfunction "g31_g31") (pintype "bidirectional"))
    )
    (net (code "133") (name "/FMC.LA_N30") (class "Default")
      (node (ref "J5") (pin "h35") (pinfunction "h35_h35") (pintype "bidirectional"))
    )
    (net (code "134") (name "/FMC.LA_N31") (class "Default")
      (node (ref "J5") (pin "g34") (pinfunction "g34_g34") (pintype "bidirectional"))
    )
    (net (code "135") (name "/FMC.LA_N32") (class "Default")
      (node (ref "J5") (pin "h38") (pinfunction "h38_h38") (pintype "bidirectional"))
    )
    (net (code "136") (name "/FMC.LA_N33") (class "Default")
      (node (ref "J5") (pin "g37") (pinfunction "g37_g37") (pintype "bidirectional"))
    )
    (net (code "138") (name "/FMC.LA_P0") (class "Default")
      (node (ref "J5") (pin "g6") (pinfunction "g6_g6") (pintype "bidirectional"))
    )
    (net (code "139") (name "/FMC.LA_P1") (class "Default")
      (node (ref "J5") (pin "d8") (pinfunction "d8_d8") (pintype "bidirectional"))
    )
    (net (code "140") (name "/FMC.LA_P2") (class "Default")
      (node (ref "J5") (pin "h7") (pinfunction "h7_h7") (pintype "bidirectional"))
    )
    (net (code "141") (name "/FMC.LA_P3") (class "Default")
      (node (ref "J5") (pin "g9") (pinfunction "g9_g9") (pintype "bidirectional"))
    )
    (net (code "142") (name "/FMC.LA_P4") (class "Default")
      (node (ref "J5") (pin "h10") (pinfunction "h10_h10") (pintype "bidirectional"))
    )
    (net (code "143") (name "/FMC.LA_P5") (class "Default")
      (node (ref "J5") (pin "d11") (pinfunction "d11_d11") (pintype "bidirectional"))
    )
    (net (code "144") (name "/FMC.LA_P6") (class "Default")
      (node (ref "J5") (pin "c10") (pinfunction "c10_c10") (pintype "bidirectional"))
    )
    (net (code "145") (name "/FMC.LA_P7") (class "Default")
      (node (ref "J5") (pin "h13") (pinfunction "h13_h13") (pintype "bidirectional"))
    )
    (net (code "146") (name "/FMC.LA_P8") (class "Default")
      (node (ref "J5") (pin "g12") (pinfunction "g12_g12") (pintype "bidirectional"))
    )
    (net (code "147") (name "/FMC.LA_P9") (class "Default")
      (node (ref "J5") (pin "d14") (pinfunction "d14_d14") (pintype "bidirectional"))
    )
    (net (code "148") (name "/FMC.LA_P10") (class "Default")
      (node (ref "J5") (pin "c14") (pinfunction "c14_c14") (pintype "bidirectional"))
    )
    (net (code "149") (name "/FMC.LA_P11") (class "Default")
      (node (ref "J5") (pin "h16") (pinfunction "h16_h16") (pintype "bidirectional"))
    )
    (net (code "150") (name "/FMC.LA_P12") (class "Default")
      (node (ref "J5") (pin "g15") (pinfunction "g15_g15") (pintype "bidirectional"))
    )
    (net (code "151") (name "/FMC.LA_P13") (class "Default")
      (node (ref "J5") (pin "d17") (pinfunction "d17_d17") (pintype "bidirectional"))
    )
    (net (code "152") (name "/FMC.LA_P14") (class "Default")
      (node (ref "J5") (pin "c18") (pinfunction "c18_c18") (pintype "bidirectional"))
    )
    (net (code "153") (name "/FMC.LA_P15") (class "Default")
      (node (ref "J5") (pin "h19") (pinfunction "h19_h19") (pintype "bidirectional"))
    )
    (net (code "154") (name "/FMC.LA_P16") (class "Default")
      (node (ref "J5") (pin "g18") (pinfunction "g18_g18") (pintype "bidirectional"))
    )
    (net (code "155") (name "/FMC.LA_P17") (class "Default")
      (node (ref "J5") (pin "d20") (pinfunction "d20_d20") (pintype "bidirectional"))
    )
    (net (code "156") (name "/FMC.LA_P18") (class "Default")
      (node (ref "J5") (pin "c22") (pinfunction "c22_c22") (pintype "bidirectional"))
    )
    (net (code "157") (name "/FMC.LA_P19") (class "Default")
      (node (ref "J5") (pin "h22") (pinfunction "h22_h22") (pintype "bidirectional"))
    )
    (net (code "158") (name "/FMC.LA_P20") (class "Default")
      (node (ref "J5") (pin "g21") (pinfunction "g21_g21") (pintype "bidirectional"))
    )
    (net (code "159") (name "/FMC.LA_P21") (class "Default")
      (node (ref "J5") (pin "h25") (pinfunction "h25_h25") (pintype "bidirectional"))
    )
    (net (code "160") (name "/FMC.LA_P22") (class "Default")
      (node (ref "J5") (pin "g24") (pinfunction "g24_g24") (pintype "bidirectional"))
    )
    (net (code "161") (name "/FMC.LA_P23") (class "Default")
      (node (ref "J5") (pin "d23") (pinfunction "d23_d23") (pintype "bidirectional"))
    )
    (net (code "162") (name "/FMC.LA_P24") (class "Default")
      (node (ref "J5") (pin "h28") (pinfunction "h28_h28") (pintype "bidirectional"))
    )
    (net (code "163") (name "/FMC.LA_P25") (class "Default")
      (node (ref "J5") (pin "g27") (pinfunction "g27_g27") (pintype "bidirectional"))
    )
    (net (code "164") (name "/FMC.LA_P26") (class "Default")
      (node (ref "J5") (pin "d26") (pinfunction "d26_d26") (pintype "bidirectional"))
    )
    (net (code "165") (name "/FMC.LA_P27") (class "Default")
      (node (ref "J5") (pin "c26") (pinfunction "c26_c26") (pintype "bidirectional"))
    )
    (net (code "166") (name "/FMC.LA_P28") (class "Default")
      (node (ref "J5") (pin "h31") (pinfunction "h31_h31") (pintype "bidirectional"))
    )
    (net (code "167") (name "/FMC.LA_P29") (class "Default")
      (node (ref "J5") (pin "g30") (pinfunction "g30_g30") (pintype "bidirectional"))
    )
    (net (code "168") (name "/FMC.LA_P30") (class "Default")
      (node (ref "J5") (pin "h34") (pinfunction "h34_h34") (pintype "bidirectional"))
    )
    (net (code "169") (name "/FMC.LA_P31") (class "Default")
      (node (ref "J5") (pin "g33") (pinfunction "g33_g33") (pintype "bidirectional"))
    )
    (net (code "170") (name "/FMC.LA_P32") (class "Default")
      (node (ref "J5") (pin "h37") (pinfunction "h37_h37") (pintype "bidirectional"))
    )
    (net (code "171") (name "/FMC.LA_P33") (class "Default")
      (node (ref "J5") (pin "g36") (pinfunction "g36_g36") (pintype "bidirectional"))
    )
    (net (code "173") (name "/FMC_CLK.CLK_BIDIR_N2") (class "Default")
      (node (ref "C211") (pin "2") (pinfunction "2_2") (pintype "passive"))
    )
    (net (code "174") (name "/FMC_CLK.CLK_BIDIR_N3") (class "Default")
      (node (ref "C216") (pin "2") (pinfunction "2_2") (pintype "passive"))
    )
    (net (code "176") (name "/FMC_CLK.CLK_BIDIR_P2") (class "Default")
      (node (ref "C210") (pin "2") (pinfunction "2_2") (pintype "passive"))
    )
    (net (code "177") (name "/FMC_CLK.CLK_BIDIR_P3") (class "Default")
      (node (ref "C215") (pin "2") (pinfunction "2_2") (pintype "passive"))
    )
    (net (code "179") (name "/FMC_CLK.CLK_M2C_N0") (class "Default")
      (node (ref "J5") (pin "h5") (pinfunction "h5_h5") (pintype "bidirectional"))
    )
    (net (code "180") (name "/FMC_CLK.CLK_M2C_N1") (class "Default")
      (node (ref "J5") (pin "g3") (pinfunction "g3_g3") (pintype "bidirectional"))
    )
    (net (code "182") (name "/FMC_CLK.CLK_M2C_P0") (class "Default")
      (node (ref "J5") (pin "h4") (pinfunction "h4_h4") (pintype "bidirectional"))
    )
    (net (code "183") (name "/FMC_CLK.CLK_M2C_P1") (class "Default")
      (node (ref "J5") (pin "g2") (pinfunction "g2_g2") (pintype "bidirectional"))
    )
    (net (code "185") (name "/FMC_CLK_BIDIR_N2") (class "Default")
      (node (ref "C211") (pin "1") (pinfunction "1_1") (pintype "passive"))
      (node (ref "C214") (pin "1") (pinfunction "1_1") (pintype "passive"))
      (node (ref "J5") (pin "k5") (pinfunction "k5_k5") (pintype "bidirectional"))
    )
    (net (code "186") (name "/FMC_CLK_BIDIR_N3") (class "Default")
      (node (ref "C216") (pin "1") (pinfunction "1_1") (pintype "passive"))
      (node (ref "C218") (pin "1") (pinfunction "1_1") (pintype "passive"))
      (node (ref "J5") (pin "j3") (pinfunction "j3_j3") (pintype "bidirectional"))
    )
    (net (code "188") (name "/FMC_CLK_BIDIR_P2") (class "Default")
      (node (ref "C210") (pin "1") (pinfunction "1_1") (pintype "passive"))
      (node (ref "C213") (pin "1") (pinfunction "1_1") (pintype "passive"))
      (node (ref "J5") (pin "k4") (pinfunction "k4_k4") (pintype "bidirectional"))
    )
    (net (code "189") (name "/FMC_CLK_BIDIR_P3") (class "Default")
      (node (ref "C215") (pin "1") (pinfunction "1_1") (pintype "passive"))
      (node (ref "C217") (pin "1") (pinfunction "1_1") (pintype "passive"))
      (node (ref "J5") (pin "j2") (pinfunction "j2_j2") (pintype "bidirectional"))
    )
    (net (code "191") (name "/FMC_CLK_DIR") (class "Default")
      (node (ref "J5") (pin "b1") (pinfunction "b1_b1") (pintype "bidirectional"))
      (node (ref "R124") (pin "2") (pinfunction "2_2") (pintype "passive"))
      (node (ref "R125") (pin "2") (pinfunction "2_2") (pintype "passive"))
    )
    (net (code "193") (name "/FMC_I2C.SCL") (class "Default")
      (node (ref "J5") (pin "c30") (pinfunction "c30_c30") (pintype "bidirectional"))
    )
    (net (code "194") (name "/FMC_I2C.SDA") (class "Default")
      (node (ref "J5") (pin "c31") (pinfunction "c31_c31") (pintype "bidirectional"))
    )
    (net (code "195") (name "/FMC_JTAG.TCK") (class "Default")
      (node (ref "J5") (pin "d29") (pinfunction "d29_d29") (pintype "bidirectional"))
    )
    (net (code "196") (name "/FMC_JTAG.TDI") (class "Default")
      (node (ref "J5") (pin "d30") (pinfunction "d30_d30") (pintype "bidirectional"))
    )
    (net (code "197") (name "/FMC_JTAG.TDO") (class "Default")
      (node (ref "J5") (pin "d31") (pinfunction "d31_d31") (pintype "bidirectional"))
    )
    (net (code "198") (name "/FMC_JTAG.TMS") (class "Default")
      (node (ref "J5") (pin "d33") (pinfunction "d33_d33") (pintype "bidirectional"))
    )
    (net (code "199") (name "/FMC_JTAG.TRSTn") (class "Default")
      (node (ref "J5") (pin "d34") (pinfunction "d34_d34") (pintype "bidirectional"))
    )
    (net (code "201") (name "/FMC_MGT.DP_C2M_N0") (class "Default")
      (node (ref "J5") (pin "c3") (pinfunction "c3_c3") (pintype "bidirectional"))
    )
    (net (code "202") (name "/FMC_MGT.DP_C2M_N1") (class "Default")
      (node (ref "J5") (pin "a23") (pinfunction "a23_a23") (pintype "bidirectional"))
    )
    (net (code "203") (name "/FMC_MGT.DP_C2M_N2") (class "Default")
      (node (ref "J5") (pin "a27") (pinfunction "a27_a27") (pintype "bidirectional"))
    )
    (net (code "204") (name "/FMC_MGT.DP_C2M_N3") (class "Default")
      (node (ref "J5") (pin "a31") (pinfunction "a31_a31") (pintype "bidirectional"))
    )
    (net (code "205") (name "/FMC_MGT.DP_C2M_N4") (class "Default")
      (node (ref "J5") (pin "a35") (pinfunction "a35_a35") (pintype "bidirectional+no_connect"))
    )
    (net (code "206") (name "/FMC_MGT.DP_C2M_N5") (class "Default")
      (node (ref "J5") (pin "a39") (pinfunction "a39_a39") (pintype "bidirectional+no_connect"))
    )
    (net (code "207") (name "/FMC_MGT.DP_C2M_N6") (class "Default")
      (node (ref "J5") (pin "b37") (pinfunction "b37_b37") (pintype "bidirectional+no_connect"))
    )
    (net (code "208") (name "/FMC_MGT.DP_C2M_N7") (class "Default")
      (node (ref "J5") (pin "b33") (pinfunction "b33_b33") (pintype "bidirectional+no_connect"))
    )
    (net (code "209") (name "/FMC_MGT.DP_C2M_N8") (class "Default")
      (node (ref "J5") (pin "b29") (pinfunction "b29_b29") (pintype "bidirectional+no_connect"))
    )
    (net (code "210") (name "/FMC_MGT.DP_C2M_N9") (class "Default")
      (node (ref "J5") (pin "b25") (pinfunction "b25_b25") (pintype "bidirectional+no_connect"))
    )
    (net (code "212") (name "/FMC_MGT.DP_C2M_P0") (class "Default")
      (node (ref "J5") (pin "c2") (pinfunction "c2_c2") (pintype "bidirectional"))
    )
    (net (code "213") (name "/FMC_MGT.DP_C2M_P1") (class "Default")
      (node (ref "J5") (pin "a22") (pinfunction "a22_a22") (pintype "bidirectional"))
    )
    (net (code "214") (name "/FMC_MGT.DP_C2M_P2") (class "Default")
      (node (ref "J5") (pin "a26") (pinfunction "a26_a26") (pintype "bidirectional"))
    )
    (net (code "215") (name "/FMC_MGT.DP_C2M_P3") (class "Default")
      (node (ref "J5") (pin "a30") (pinfunction "a30_a30") (pintype "bidirectional"))
    )
    (net (code "216") (name "/FMC_MGT.DP_C2M_P4") (class "Default")
      (node (ref "J5") (pin "a34") (pinfunction "a34_a34") (pintype "bidirectional+no_connect"))
    )
    (net (code "217") (name "/FMC_MGT.DP_C2M_P5") (class "Default")
      (node (ref "J5") (pin "a38") (pinfunction "a38_a38") (pintype "bidirectional+no_connect"))
    )
    (net (code "218") (name "/FMC_MGT.DP_C2M_P6") (class "Default")
      (node (ref "J5") (pin "b36") (pinfunction "b36_b36") (pintype "bidirectional+no_connect"))
    )
    (net (code "219") (name "/FMC_MGT.DP_C2M_P7") (class "Default")
      (node (ref "J5") (pin "b32") (pinfunction "b32_b32") (pintype "bidirectional+no_connect"))
    )
    (net (code "220") (name "/FMC_MGT.DP_C2M_P8") (class "Default")
      (node (ref "J5") (pin "b28") (pinfunction "b28_b28") (pintype "bidirectional+no_connect"))
    )
    (net (code "221") (name "/FMC_MGT.DP_C2M_P9") (class "Default")
      (node (ref "J5") (pin "b24") (pinfunction "b24_b24") (pintype "bidirectional+no_connect"))
    )
    (net (code "223") (name "/FMC_MGT.DP_M2C_N0") (class "Default")
      (node (ref "J5") (pin "c7") (pinfunction "c7_c7") (pintype "bidirectional"))
    )
    (net (code "224") (name "/FMC_MGT.DP_M2C_N1") (class "Default")
      (node (ref "J5") (pin "a3") (pinfunction "a3_a3") (pintype "bidirectional"))
    )
    (net (code "225") (name "/FMC_MGT.DP_M2C_N2") (class "Default")
      (node (ref "J5") (pin "a7") (pinfunction "a7_a7") (pintype "bidirectional"))
    )
    (net (code "226") (name "/FMC_MGT.DP_M2C_N3") (class "Default")
      (node (ref "J5") (pin "a11") (pinfunction "a11_a11") (pintype "bidirectional"))
    )
    (net (code "227") (name "/FMC_MGT.DP_M2C_N4") (class "Default")
      (node (ref "J5") (pin "a15") (pinfunction "a15_a15") (pintype "bidirectional+no_connect"))
    )
    (net (code "228") (name "/FMC_MGT.DP_M2C_N5") (class "Default")
      (node (ref "J5") (pin "a19") (pinfunction "a19_a19") (pintype "bidirectional+no_connect"))
    )
    (net (code "229") (name "/FMC_MGT.DP_M2C_N6") (class "Default")
      (node (ref "J5") (pin "b17") (pinfunction "b17_b17") (pintype "bidirectional+no_connect"))
    )
    (net (code "230") (name "/FMC_MGT.DP_M2C_N7") (class "Default")
      (node (ref "J5") (pin "b13") (pinfunction "b13_b13") (pintype "bidirectional+no_connect"))
    )
    (net (code "231") (name "/FMC_MGT.DP_M2C_N8") (class "Default")
      (node (ref "J5") (pin "b9") (pinfunction "b9_b9") (pintype "bidirectional+no_connect"))
    )
    (net (code "232") (name "/FMC_MGT.DP_M2C_N9") (class "Default")
      (node (ref "J5") (pin "b5") (pinfunction "b5_b5") (pintype "bidirectional+no_connect"))
    )
    (net (code "234") (name "/FMC_MGT.DP_M2C_P0") (class "Default")
      (node (ref "J5") (pin "c6") (pinfunction "c6_c6") (pintype "bidirectional"))
    )
    (net (code "235") (name "/FMC_MGT.DP_M2C_P1") (class "Default")
      (node (ref "J5") (pin "a2") (pinfunction "a2_a2") (pintype "bidirectional"))
    )
    (net (code "236") (name "/FMC_MGT.DP_M2C_P2") (class "Default")
      (node (ref "J5") (pin "a6") (pinfunction "a6_a6") (pintype "bidirectional"))
    )
    (net (code "237") (name "/FMC_MGT.DP_M2C_P3") (class "Default")
      (node (ref "J5") (pin "a10") (pinfunction "a10_a10") (pintype "bidirectional"))
    )
    (net (code "238") (name "/FMC_MGT.DP_M2C_P4") (class "Default")
      (node (ref "J5") (pin "a14") (pinfunction "a14_a14") (pintype "bidirectional+no_connect"))
    )
    (net (code "239") (name "/FMC_MGT.DP_M2C_P5") (class "Default")
      (node (ref "J5") (pin "a18") (pinfunction "a18_a18") (pintype "bidirectional+no_connect"))
    )
    (net (code "240") (name "/FMC_MGT.DP_M2C_P6") (class "Default")
      (node (ref "J5") (pin "b16") (pinfunction "b16_b16") (pintype "bidirectional+no_connect"))
    )
    (net (code "241") (name "/FMC_MGT.DP_M2C_P7") (class "Default")
      (node (ref "J5") (pin "b12") (pinfunction "b12_b12") (pintype "bidirectional+no_connect"))
    )
    (net (code "242") (name "/FMC_MGT.DP_M2C_P8") (class "Default")
      (node (ref "J5") (pin "b8") (pinfunction "b8_b8") (pintype "bidirectional+no_connect"))
    )
    (net (code "243") (name "/FMC_MGT.DP_M2C_P9") (class "Default")
      (node (ref "J5") (pin "b4") (pinfunction "b4_b4") (pintype "bidirectional+no_connect"))
    )
    (net (code "245") (name "/FMC_MGT.GBTCLK_M2C_N0") (class "Default")
      (node (ref "C200") (pin "2") (pinfunction "2_2") (pintype "passive"))
    )
    (net (code "246") (name "/FMC_MGT.GBTCLK_M2C_N1") (class "Default")
      (node (ref "J5") (pin "b21") (pinfunction "b21_b21") (pintype "bidirectional+no_connect"))
    )
    (net (code "248") (name "/FMC_MGT.GBTCLK_M2C_P0") (class "Default")
      (node (ref "C199") (pin "2") (pinfunction "2_2") (pintype "passive"))
    )
    (net (code "249") (name "/FMC_MGT.GBTCLK_M2C_P1") (class "Default")
      (node (ref "J5") (pin "b20") (pinfunction "b20_b20") (pintype "bidirectional+no_connect"))
    )
    (net (code "252") (name "/FMC_PG_C2M") (class "Default")
      (node (ref "J5") (pin "d1") (pinfunction "d1_d1") (pintype "bidirectional"))
      (node (ref "R123") (pin "1") (pinfunction "1_1") (pintype "passive"))
    )
    (net (code "253") (name "/FMC_PG_M2C") (class "Default")
      (node (ref "J5") (pin "f1") (pinfunction "f1_f1") (pintype "bidirectional"))
      (node (ref "R122") (pin "1") (pinfunction "1_1") (pintype "passive"))
    )
    (net (code "254") (name "/FMC_PS_N") (class "Default")
      (node (ref "J5") (pin "h2") (pinfunction "h2_h2") (pintype "bidirectional"))
      (node (ref "R121") (pin "1") (pinfunction "1_1") (pintype "passive"))
    )
    (net (code "255") (name "/FMC_REF0_CLK.CLK_N") (class "Default")
      (node (ref "C214") (pin "2") (pinfunction "2_2") (pintype "passive"))
    )
    (net (code "256") (name "/FMC_REF0_CLK.CLK_P") (class "Default")
      (node (ref "C213") (pin "2") (pinfunction "2_2") (pintype "passive"))
    )
    (net (code "257") (name "/FMC_REF1_CLK.CLK_N") (class "Default")
      (node (ref "C218") (pin "2") (pinfunction "2_2") (pintype "passive"))
    )
    (net (code "258") (name "/FMC_REF1_CLK.CLK_P") (class "Default")
      (node (ref "C217") (pin "2") (pinfunction "2_2") (pintype "passive"))
    )
    (net (code "260") (name "/GBTCLK0_M2C_N") (class "Default")
      (node (ref "C200") (pin "1") (pinfunction "1_1") (pintype "passive"))
      (node (ref "J5") (pin "d5") (pinfunction "d5_d5") (pintype "bidirectional"))
    )
    (net (code "261") (name "/GBTCLK0_M2C_P") (class "Default")
      (node (ref "C199") (pin "1") (pinfunction "1_1") (pintype "passive"))
      (node (ref "J5") (pin "d4") (pinfunction "d4_d4") (pintype "bidirectional"))
    )
    (net (code "264") (name "FMC_VIO_B_M2C") (class "Default")
      (node (ref "J5") (pin "j39") (pinfunction "j39_j39") (pintype "bidirectional"))
      (node (ref "J5") (pin "k40") (pinfunction "k40_k40") (pintype "bidirectional"))
    )
    (net (code "265") (name "FMC_VREFA_M2C") (class "Default")
      (node (ref "J5") (pin "h1") (pinfunction "h1_h1") (pintype "bidirectional"))
    )
    (net (code "266") (name "FMC_VREFB_M2C") (class "Default")
      (node (ref "J5") (pin "k1") (pinfunction "k1_k1") (pintype "bidirectional"))
    )
    (net (code "267") (name "GND") (class "Default")
      (node (ref "C171") (pin "1") (pinfunction "1_1") (pintype "passive"))
      (node (ref "C176") (pin "1") (pinfunction "1_1") (pintype "passive"))
      (node (ref "C193") (pin "1") (pinfunction "1_1") (pintype "passive"))
      (node (ref "C194") (pin "1") (pinfunction "1_1") (pintype "passive"))
      (node (ref "C195") (pin "1") (pinfunction "1_1") (pintype "passive"))
      (node (ref "C196") (pin "1") (pinfunction "1_1") (pintype "passive"))
      (node (ref "C197") (pin "2") (pinfunction "2_2") (pintype "passive"))
      (node (ref "C198") (pin "2") (pinfunction "2_2") (pintype "passive"))
      (node (ref "C203") (pin "1") (pinfunction "1_1") (pintype "passive"))
      (node (ref "C204") (pin "2") (pinfunction "2_2") (pintype "passive"))
      (node (ref "C205") (pin "2") (pinfunction "2_2") (pintype "passive"))
      (node (ref "C206") (pin "1") (pinfunction "1_1") (pintype "passive"))
      (node (ref "C207") (pin "1") (pinfunction "1_1") (pintype "passive"))
      (node (ref "C208") (pin "2") (pinfunction "2_2") (pintype "passive"))
      (node (ref "C209") (pin "2") (pinfunction "2_2") (pintype "passive"))
      (node (ref "C290") (pin "1") (pinfunction "1_1") (pintype "passive"))
      (node (ref "C291") (pin "1") (pinfunction "1_1") (pintype "passive"))
      (node (ref "C292") (pin "1") (pinfunction "1_1") (pintype "passive"))
      (node (ref "C293") (pin "1") (pinfunction "1_1") (pintype "passive"))
      (node (ref "C294") (pin "1") (pinfunction "1_1") (pintype "passive"))
      (node (ref "C295") (pin "1") (pinfunction "1_1") (pintype "passive"))
      (node (ref "C296") (pin "1") (pinfunction "1_1") (pintype "passive"))
      (node (ref "C297") (pin "1") (pinfunction "1_1") (pintype "passive"))
      (node (ref "J5") (pin "a1") (pinfunction "a1_a1") (pintype "bidirectional"))
      (node (ref "J5") (pin "a12") (pinfunction "a12_a12") (pintype "bidirectional"))
      (node (ref "J5") (pin "a13") (pinfunction "a13_a13") (pintype "bidirectional"))
      (node (ref "J5") (pin "a16") (pinfunction "a16_a16") (pintype "bidirectional"))
      (node (ref "J5") (pin "a17") (pinfunction "a17_a17") (pintype "bidirectional"))
      (node (ref "J5") (pin "a20") (pinfunction "a20_a20") (pintype "bidirectional"))
      (node (ref "J5") (pin "a21") (pinfunction "a21_a21") (pintype "bidirectional"))
      (node (ref "J5") (pin "a24") (pinfunction "a24_a24") (pintype "bidirectional"))
      (node (ref "J5") (pin "a25") (pinfunction "a25_a25") (pintype "bidirectional"))
      (node (ref "J5") (pin "a28") (pinfunction "a28_a28") (pintype "bidirectional"))
      (node (ref "J5") (pin "a29") (pinfunction "a29_a29") (pintype "bidirectional"))
      (node (ref "J5") (pin "a32") (pinfunction "a32_a32") (pintype "bidirectional"))
      (node (ref "J5") (pin "a33") (pinfunction "a33_a33") (pintype "bidirectional"))
      (node (ref "J5") (pin "a36") (pinfunction "a36_a36") (pintype "bidirectional"))
      (node (ref "J5") (pin "a37") (pinfunction "a37_a37") (pintype "bidirectional"))
      (node (ref "J5") (pin "a4") (pinfunction "a4_a4") (pintype "bidirectional"))
      (node (ref "J5") (pin "a40") (pinfunction "a40_a40") (pintype "bidirectional"))
      (node (ref "J5") (pin "a5") (pinfunction "a5_a5") (pintype "bidirectional"))
      (node (ref "J5") (pin "a8") (pinfunction "a8_a8") (pintype "bidirectional"))
      (node (ref "J5") (pin "a9") (pinfunction "a9_a9") (pintype "bidirectional"))
      (node (ref "J5") (pin "b10") (pinfunction "b10_b10") (pintype "bidirectional"))
      (node (ref "J5") (pin "b11") (pinfunction "b11_b11") (pintype "bidirectional"))
      (node (ref "J5") (pin "b14") (pinfunction "b14_b14") (pintype "bidirectional"))
      (node (ref "J5") (pin "b15") (pinfunction "b15_b15") (pintype "bidirectional"))
      (node (ref "J5") (pin "b18") (pinfunction "b18_b18") (pintype "bidirectional"))
      (node (ref "J5") (pin "b19") (pinfunction "b19_b19") (pintype "bidirectional"))
      (node (ref "J5") (pin "b2") (pinfunction "b2_b2") (pintype "bidirectional"))
      (node (ref "J5") (pin "b22") (pinfunction "b22_b22") (pintype "bidirectional"))
      (node (ref "J5") (pin "b23") (pinfunction "b23_b23") (pintype "bidirectional"))
      (node (ref "J5") (pin "b26") (pinfunction "b26_b26") (pintype "bidirectional"))
      (node (ref "J5") (pin "b27") (pinfunction "b27_b27") (pintype "bidirectional"))
      (node (ref "J5") (pin "b3") (pinfunction "b3_b3") (pintype "bidirectional"))
      (node (ref "J5") (pin "b30") (pinfunction "b30_b30") (pintype "bidirectional"))
      (node (ref "J5") (pin "b31") (pinfunction "b31_b31") (pintype "bidirectional"))
      (node (ref "J5") (pin "b34") (pinfunction "b34_b34") (pintype "bidirectional"))
      (node (ref "J5") (pin "b35") (pinfunction "b35_b35") (pintype "bidirectional"))
      (node (ref "J5") (pin "b38") (pinfunction "b38_b38") (pintype "bidirectional"))
      (node (ref "J5") (pin "b39") (pinfunction "b39_b39") (pintype "bidirectional"))
      (node (ref "J5") (pin "b6") (pinfunction "b6_b6") (pintype "bidirectional"))
      (node (ref "J5") (pin "b7") (pinfunction "b7_b7") (pintype "bidirectional"))
      (node (ref "J5") (pin "c1") (pinfunction "c1_c1") (pintype "bidirectional"))
      (node (ref "J5") (pin "c12") (pinfunction "c12_c12") (pintype "bidirectional"))
      (node (ref "J5") (pin "c13") (pinfunction "c13_c13") (pintype "bidirectional"))
      (node (ref "J5") (pin "c16") (pinfunction "c16_c16") (pintype "bidirectional"))
      (node (ref "J5") (pin "c17") (pinfunction "c17_c17") (pintype "bidirectional"))
      (node (ref "J5") (pin "c20") (pinfunction "c20_c20") (pintype "bidirectional"))
      (node (ref "J5") (pin "c21") (pinfunction "c21_c21") (pintype "bidirectional"))
      (node (ref "J5") (pin "c24") (pinfunction "c24_c24") (pintype "bidirectional"))
      (node (ref "J5") (pin "c25") (pinfunction "c25_c25") (pintype "bidirectional"))
      (node (ref "J5") (pin "c28") (pinfunction "c28_c28") (pintype "bidirectional"))
      (node (ref "J5") (pin "c29") (pinfunction "c29_c29") (pintype "bidirectional"))
      (node (ref "J5") (pin "c32") (pinfunction "c32_c32") (pintype "bidirectional"))
      (node (ref "J5") (pin "c33") (pinfunction "c33_c33") (pintype "bidirectional"))
      (node (ref "J5") (pin "c34") (pinfunction "c34_c34") (pintype "bidirectional"))
      (node (ref "J5") (pin "c36") (pinfunction "c36_c36") (pintype "bidirectional"))
      (node (ref "J5") (pin "c38") (pinfunction "c38_c38") (pintype "bidirectional"))
      (node (ref "J5") (pin "c4") (pinfunction "c4_c4") (pintype "bidirectional"))
      (node (ref "J5") (pin "c40") (pinfunction "c40_c40") (pintype "bidirectional"))
      (node (ref "J5") (pin "c5") (pinfunction "c5_c5") (pintype "bidirectional"))
      (node (ref "J5") (pin "c8") (pinfunction "c8_c8") (pintype "bidirectional"))
      (node (ref "J5") (pin "c9") (pinfunction "c9_c9") (pintype "bidirectional"))
      (node (ref "J5") (pin "d10") (pinfunction "d10_d10") (pintype "bidirectional"))
      (node (ref "J5") (pin "d13") (pinfunction "d13_d13") (pintype "bidirectional"))
      (node (ref "J5") (pin "d16") (pinfunction "d16_d16") (pintype "bidirectional"))
      (node (ref "J5") (pin "d19") (pinfunction "d19_d19") (pintype "bidirectional"))
      (node (ref "J5") (pin "d2") (pinfunction "d2_d2") (pintype "bidirectional"))
      (node (ref "J5") (pin "d22") (pinfunction "d22_d22") (pintype "bidirectional"))
      (node (ref "J5") (pin "d25") (pinfunction "d25_d25") (pintype "bidirectional"))
      (node (ref "J5") (pin "d28") (pinfunction "d28_d28") (pintype "bidirectional"))
      (node (ref "J5") (pin "d3") (pinfunction "d3_d3") (pintype "bidirectional"))
      (node (ref "J5") (pin "d35") (pinfunction "d35_d35") (pintype "bidirectional"))
      (node (ref "J5") (pin "d37") (pinfunction "d37_d37") (pintype "bidirectional"))
      (node (ref "J5") (pin "d39") (pinfunction "d39_d39") (pintype "bidirectional"))
      (node (ref "J5") (pin "d6") (pinfunction "d6_d6") (pintype "bidirectional"))
      (node (ref "J5") (pin "d7") (pinfunction "d7_d7") (pintype "bidirectional"))
      (node (ref "J5") (pin "e1") (pinfunction "e1_e1") (pintype "bidirectional"))
      (node (ref "J5") (pin "e11") (pinfunction "e11_e11") (pintype "bidirectional"))
      (node (ref "J5") (pin "e14") (pinfunction "e14_e14") (pintype "bidirectional"))
      (node (ref "J5") (pin "e17") (pinfunction "e17_e17") (pintype "bidirectional"))
      (node (ref "J5") (pin "e20") (pinfunction "e20_e20") (pintype "bidirectional"))
      (node (ref "J5") (pin "e23") (pinfunction "e23_e23") (pintype "bidirectional"))
      (node (ref "J5") (pin "e26") (pinfunction "e26_e26") (pintype "bidirectional"))
      (node (ref "J5") (pin "e29") (pinfunction "e29_e29") (pintype "bidirectional"))
      (node (ref "J5") (pin "e32") (pinfunction "e32_e32") (pintype "bidirectional"))
      (node (ref "J5") (pin "e35") (pinfunction "e35_e35") (pintype "bidirectional"))
      (node (ref "J5") (pin "e38") (pinfunction "e38_e38") (pintype "bidirectional"))
      (node (ref "J5") (pin "e4") (pinfunction "e4_e4") (pintype "bidirectional"))
      (node (ref "J5") (pin "e40") (pinfunction "e40_e40") (pintype "bidirectional"))
      (node (ref "J5") (pin "e5") (pinfunction "e5_e5") (pintype "bidirectional"))
      (node (ref "J5") (pin "e8") (pinfunction "e8_e8") (pintype "bidirectional"))
      (node (ref "J5") (pin "f12") (pinfunction "f12_f12") (pintype "bidirectional"))
      (node (ref "J5") (pin "f15") (pinfunction "f15_f15") (pintype "bidirectional"))
      (node (ref "J5") (pin "f18") (pinfunction "f18_f18") (pintype "bidirectional"))
      (node (ref "J5") (pin "f2") (pinfunction "f2_f2") (pintype "bidirectional"))
      (node (ref "J5") (pin "f21") (pinfunction "f21_f21") (pintype "bidirectional"))
      (node (ref "J5") (pin "f24") (pinfunction "f24_f24") (pintype "bidirectional"))
      (node (ref "J5") (pin "f27") (pinfunction "f27_f27") (pintype "bidirectional"))
      (node (ref "J5") (pin "f3") (pinfunction "f3_f3") (pintype "bidirectional"))
      (node (ref "J5") (pin "f30") (pinfunction "f30_f30") (pintype "bidirectional"))
      (node (ref "J5") (pin "f33") (pinfunction "f33_f33") (pintype "bidirectional"))
      (node (ref "J5") (pin "f36") (pinfunction "f36_f36") (pintype "bidirectional"))
      (node (ref "J5") (pin "f39") (pinfunction "f39_f39") (pintype "bidirectional"))
      (node (ref "J5") (pin "f6") (pinfunction "f6_f6") (pintype "bidirectional"))
      (node (ref "J5") (pin "f9") (pinfunction "f9_f9") (pintype "bidirectional"))
      (node (ref "J5") (pin "g1") (pinfunction "g1_g1") (pintype "bidirectional"))
      (node (ref "J5") (pin "g11") (pinfunction "g11_g11") (pintype "bidirectional"))
      (node (ref "J5") (pin "g14") (pinfunction "g14_g14") (pintype "bidirectional"))
      (node (ref "J5") (pin "g17") (pinfunction "g17_g17") (pintype "bidirectional"))
      (node (ref "J5") (pin "g20") (pinfunction "g20_g20") (pintype "bidirectional"))
      (node (ref "J5") (pin "g23") (pinfunction "g23_g23") (pintype "bidirectional"))
      (node (ref "J5") (pin "g26") (pinfunction "g26_g26") (pintype "bidirectional"))
      (node (ref "J5") (pin "g29") (pinfunction "g29_g29") (pintype "bidirectional"))
      (node (ref "J5") (pin "g32") (pinfunction "g32_g32") (pintype "bidirectional"))
      (node (ref "J5") (pin "g35") (pinfunction "g35_g35") (pintype "bidirectional"))
      (node (ref "J5") (pin "g38") (pinfunction "g38_g38") (pintype "bidirectional"))
      (node (ref "J5") (pin "g4") (pinfunction "g4_g4") (pintype "bidirectional"))
      (node (ref "J5") (pin "g40") (pinfunction "g40_g40") (pintype "bidirectional"))
      (node (ref "J5") (pin "g5") (pinfunction "g5_g5") (pintype "bidirectional"))
      (node (ref "J5") (pin "g8") (pinfunction "g8_g8") (pintype "bidirectional"))
      (node (ref "J5") (pin "h12") (pinfunction "h12_h12") (pintype "bidirectional"))
      (node (ref "J5") (pin "h15") (pinfunction "h15_h15") (pintype "bidirectional"))
      (node (ref "J5") (pin "h18") (pinfunction "h18_h18") (pintype "bidirectional"))
      (node (ref "J5") (pin "h21") (pinfunction "h21_h21") (pintype "bidirectional"))
      (node (ref "J5") (pin "h24") (pinfunction "h24_h24") (pintype "bidirectional"))
      (node (ref "J5") (pin "h27") (pinfunction "h27_h27") (pintype "bidirectional"))
      (node (ref "J5") (pin "h3") (pinfunction "h3_h3") (pintype "bidirectional"))
      (node (ref "J5") (pin "h30") (pinfunction "h30_h30") (pintype "bidirectional"))
      (node (ref "J5") (pin "h33") (pinfunction "h33_h33") (pintype "bidirectional"))
      (node (ref "J5") (pin "h36") (pinfunction "h36_h36") (pintype "bidirectional"))
      (node (ref "J5") (pin "h39") (pinfunction "h39_h39") (pintype "bidirectional"))
      (node (ref "J5") (pin "h6") (pinfunction "h6_h6") (pintype "bidirectional"))
      (node (ref "J5") (pin "h9") (pinfunction "h9_h9") (pintype "bidirectional"))
      (node (ref "J5") (pin "j1") (pinfunction "j1_j1") (pintype "bidirectional"))
      (node (ref "J5") (pin "j11") (pinfunction "j11_j11") (pintype "bidirectional"))
      (node (ref "J5") (pin "j14") (pinfunction "j14_j14") (pintype "bidirectional"))
      (node (ref "J5") (pin "j17") (pinfunction "j17_j17") (pintype "bidirectional"))
      (node (ref "J5") (pin "j20") (pinfunction "j20_j20") (pintype "bidirectional"))
      (node (ref "J5") (pin "j23") (pinfunction "j23_j23") (pintype "bidirectional"))
      (node (ref "J5") (pin "j26") (pinfunction "j26_j26") (pintype "bidirectional"))
      (node (ref "J5") (pin "j29") (pinfunction "j29_j29") (pintype "bidirectional"))
      (node (ref "J5") (pin "j32") (pinfunction "j32_j32") (pintype "bidirectional"))
      (node (ref "J5") (pin "j35") (pinfunction "j35_j35") (pintype "bidirectional"))
      (node (ref "J5") (pin "j38") (pinfunction "j38_j38") (pintype "bidirectional"))
      (node (ref "J5") (pin "j4") (pinfunction "j4_j4") (pintype "bidirectional"))
      (node (ref "J5") (pin "j40") (pinfunction "j40_j40") (pintype "bidirectional"))
      (node (ref "J5") (pin "j5") (pinfunction "j5_j5") (pintype "bidirectional"))
      (node (ref "J5") (pin "j8") (pinfunction "j8_j8") (pintype "bidirectional"))
      (node (ref "J5") (pin "k12") (pinfunction "k12_k12") (pintype "bidirectional"))
      (node (ref "J5") (pin "k15") (pinfunction "k15_k15") (pintype "bidirectional"))
      (node (ref "J5") (pin "k18") (pinfunction "k18_k18") (pintype "bidirectional"))
      (node (ref "J5") (pin "k2") (pinfunction "k2_k2") (pintype "bidirectional"))
      (node (ref "J5") (pin "k21") (pinfunction "k21_k21") (pintype "bidirectional"))
      (node (ref "J5") (pin "k24") (pinfunction "k24_k24") (pintype "bidirectional"))
      (node (ref "J5") (pin "k27") (pinfunction "k27_k27") (pintype "bidirectional"))
      (node (ref "J5") (pin "k3") (pinfunction "k3_k3") (pintype "bidirectional"))
      (node (ref "J5") (pin "k30") (pinfunction "k30_k30") (pintype "bidirectional"))
      (node (ref "J5") (pin "k33") (pinfunction "k33_k33") (pintype "bidirectional"))
      (node (ref "J5") (pin "k36") (pinfunction "k36_k36") (pintype "bidirectional"))
      (node (ref "J5") (pin "k39") (pinfunction "k39_k39") (pintype "bidirectional"))
      (node (ref "J5") (pin "k6") (pinfunction "k6_k6") (pintype "bidirectional"))
      (node (ref "J5") (pin "k9") (pinfunction "k9_k9") (pintype "bidirectional"))
      (node (ref "R124") (pin "1") (pinfunction "1_1") (pintype "passive"))
      (node (ref "R125") (pin "1") (pinfunction "1_1") (pintype "passive"))
    )
    (net (code "268") (name "P3V3") (class "Default")
      (node (ref "C203") (pin "2") (pinfunction "2_2") (pintype "passive"))
      (node (ref "J5") (pin "d32") (pinfunction "d32_d32") (pintype "bidirectional"))
      (node (ref "R121") (pin "2") (pinfunction "2_2") (pintype "passive"))
      (node (ref "R122") (pin "2") (pinfunction "2_2") (pintype "passive"))
      (node (ref "R123") (pin "2") (pinfunction "2_2") (pintype "passive"))
    )
    (net (code "269") (name "P3V3_FMC") (class "Default")
      (node (ref "C207") (pin "2") (pinfunction "2_2") (pintype "passive"))
      (node (ref "C208") (pin "1") (pinfunction "1_1") (pintype "passive"))
      (node (ref "C209") (pin "1") (pinfunction "1_1") (pintype "passive"))
      (node (ref "J5") (pin "c39") (pinfunction "c39_c39") (pintype "bidirectional"))
      (node (ref "J5") (pin "d36") (pinfunction "d36_d36") (pintype "bidirectional"))
      (node (ref "J5") (pin "d38") (pinfunction "d38_d38") (pintype "bidirectional"))
      (node (ref "J5") (pin "d40") (pinfunction "d40_d40") (pintype "bidirectional"))
    )
    (net (code "270") (name "P12V0") (class "Default")
      (node (ref "C204") (pin "1") (pinfunction "1_1") (pintype "passive"))
      (node (ref "C205") (pin "1") (pinfunction "1_1") (pintype "passive"))
      (node (ref "J5") (pin "c35") (pinfunction "c35_c35") (pintype "bidirectional"))
      (node (ref "J5") (pin "c37") (pinfunction "c37_c37") (pintype "bidirectional"))
    )
    (net (code "271") (name "VADJ_FMC") (class "Default")
      (node (ref "C171") (pin "2") (pinfunction "2_2") (pintype "passive"))
      (node (ref "C176") (pin "2") (pinfunction "2_2") (pintype "passive"))
      (node (ref "C193") (pin "2") (pinfunction "2_2") (pintype "passive"))
      (node (ref "C194") (pin "2") (pinfunction "2_2") (pintype "passive"))
      (node (ref "C195") (pin "2") (pinfunction "2_2") (pintype "passive"))
      (node (ref "C196") (pin "2") (pinfunction "2_2") (pintype "passive"))
      (node (ref "C197") (pin "1") (pinfunction "1_1") (pintype "passive"))
      (node (ref "C198") (pin "1") (pinfunction "1_1") (pintype "passive"))
      (node (ref "C206") (pin "2") (pinfunction "2_2") (pintype "passive"))
      (node (ref "C290") (pin "2") (pinfunction "2_2") (pintype "passive"))
      (node (ref "C291") (pin "2") (pinfunction "2_2") (pintype "passive"))
      (node (ref "C292") (pin "2") (pinfunction "2_2") (pintype "passive"))
      (node (ref "C293") (pin "2") (pinfunction "2_2") (pintype "passive"))
      (node (ref "C294") (pin "2") (pinfunction "2_2") (pintype "passive"))
      (node (ref "C295") (pin "2") (pinfunction "2_2") (pintype "passive"))
      (node (ref "C296") (pin "2") (pinfunction "2_2") (pintype "passive"))
      (node (ref "C297") (pin "2") (pinfunction "2_2") (pintype "passive"))
      (node (ref "J5") (pin "e39") (pinfunction "e39_e39") (pintype "bidirectional"))
      (node (ref "J5") (pin "f40") (pinfunction "f40_f40") (pintype "bidirectional"))
      (node (ref "J5") (pin "g39") (pinfunction "g39_g39") (pintype "bidirectional"))
      (node (ref "J5") (pin "h40") (pinfunction "h40_h40") (pintype "bidirectional"))
    )
    (net (code "272") (name "unconnected-(J5-Padb40)") (class "Default")
      (node (ref "J5") (pin "b40") (pinfunction "b40_b40") (pintype "bidirectional+no_connect"))
    )
  )
)
